# CBMINICONN.net
KiCad netlist of a schematic drawn in EAGLE
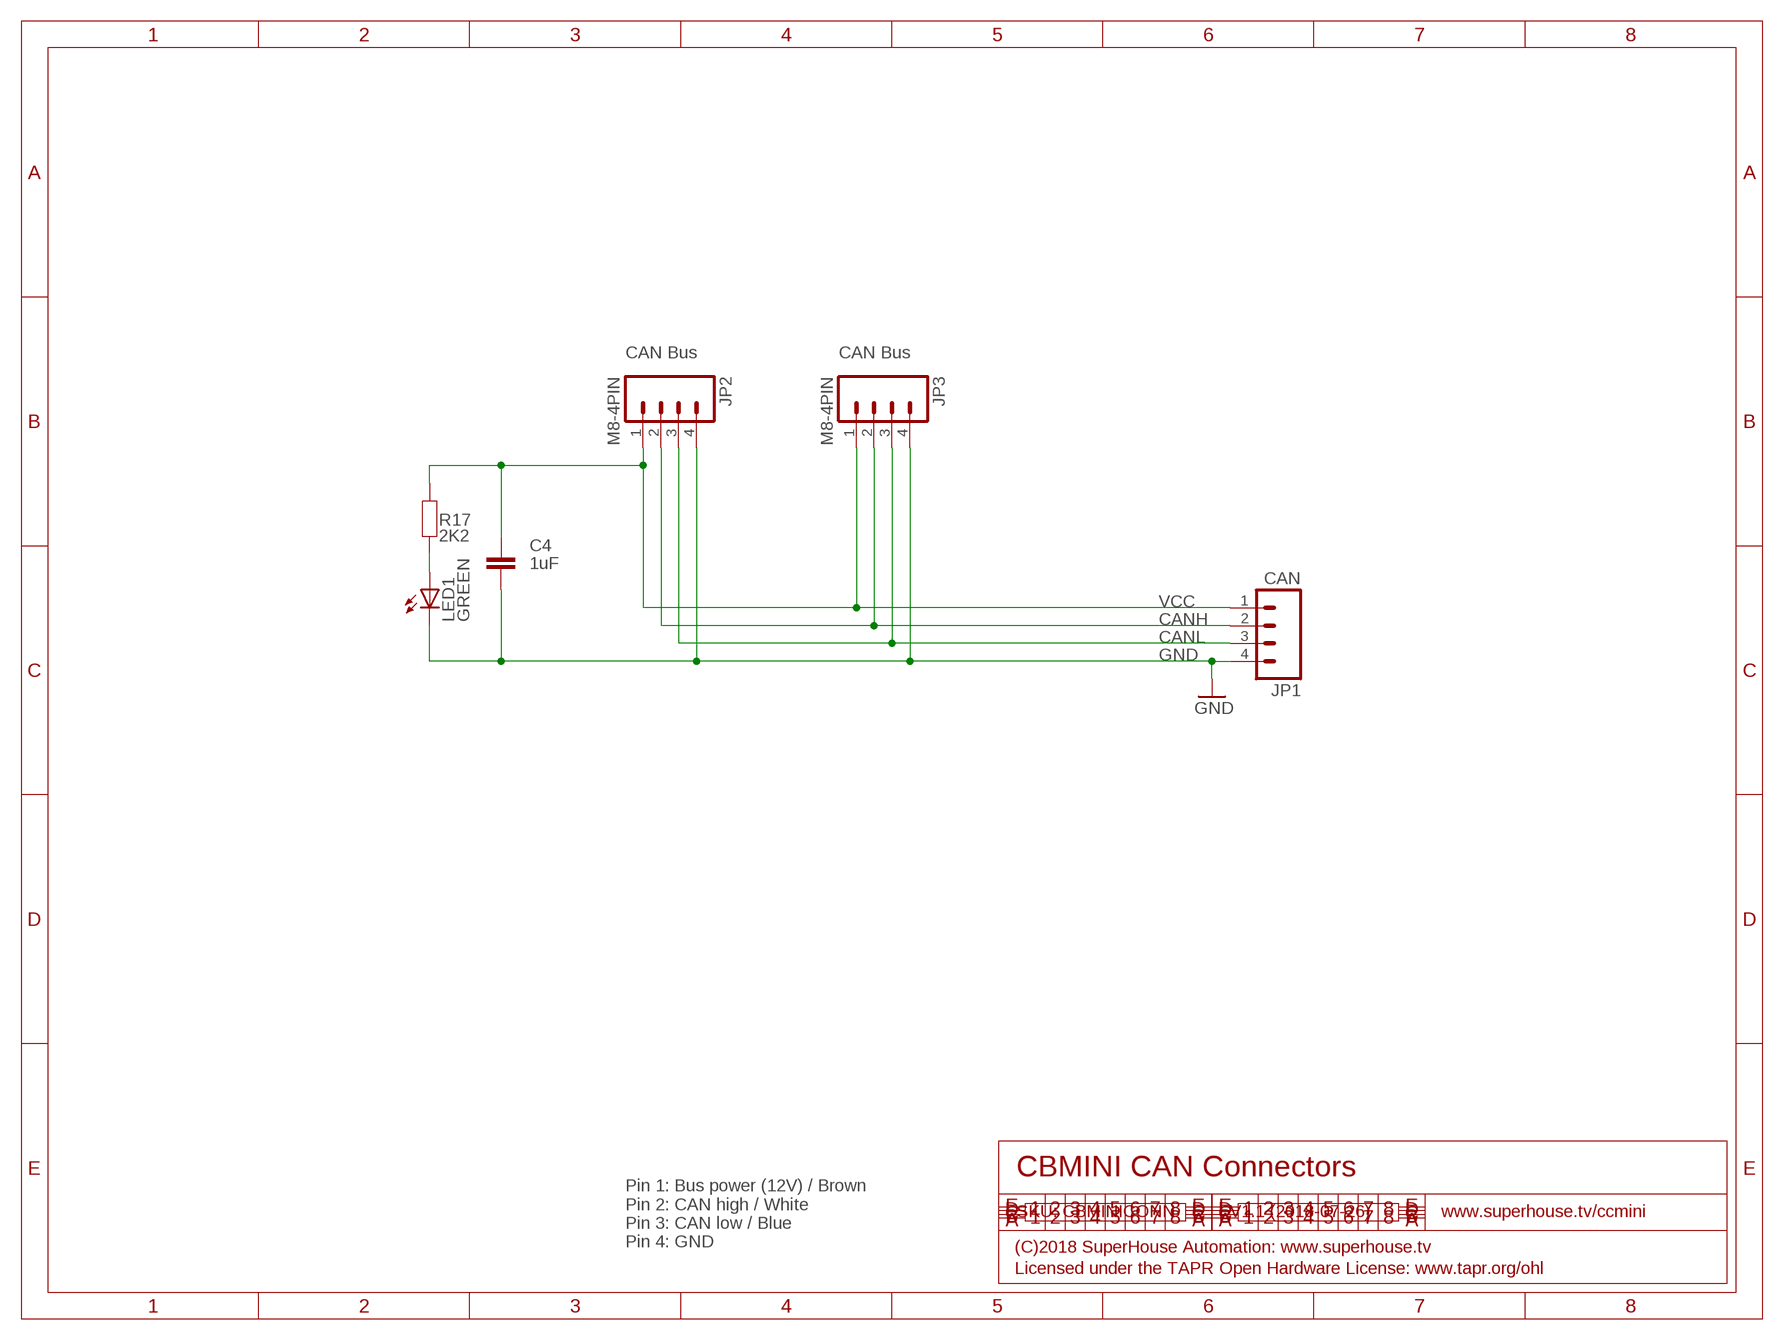
[diagram p0: schematic, sheet 1]

(export (version "E")
  (design (tool "Eeschema 10.0.6"))
  (components
    (comp (ref "C4")
      (value "1uF")
      (footprint "eagle-import:0603")
      (libsource (lib "eagle-import") (part "CAP0603"))
    )
    (comp (ref "JP1")
      (value "CAN")
      (footprint "eagle-import:1X04")
      (libsource (lib "eagle-import") (part "M04PTH"))
    )
    (comp (ref "JP2")
      (value "M8-4PIN")
      (footprint "eagle-import:M8-4PIN")
      (libsource (lib "eagle-import") (part "M8-4PIN"))
    )
    (comp (ref "JP3")
      (value "M8-4PIN")
      (footprint "eagle-import:M8-4PIN")
      (libsource (lib "eagle-import") (part "M8-4PIN"))
    )
    (comp (ref "LED1")
      (value "GREEN")
      (footprint "eagle-import:LED3MM")
      (libsource (lib "eagle-import") (part "LED3MM"))
    )
    (comp (ref "R17")
      (value "2K2")
      (footprint "eagle-import:0603")
      (libsource (lib "eagle-import") (part "RESISTOR0603"))
    )
  )
  (nets
    (net (code "1") (name "/CANH") (class "Default")
      (node (ref "JP1") (pin "2") (pinfunction "2_2") (pintype "passive"))
      (node (ref "JP2") (pin "2") (pinfunction "2_2") (pintype "passive"))
      (node (ref "JP3") (pin "2") (pinfunction "2_2") (pintype "passive"))
    )
    (net (code "2") (name "/CANL") (class "Default")
      (node (ref "JP1") (pin "3") (pinfunction "3_3") (pintype "passive"))
      (node (ref "JP2") (pin "3") (pinfunction "3_3") (pintype "passive"))
      (node (ref "JP3") (pin "3") (pinfunction "3_3") (pintype "passive"))
    )
    (net (code "3") (name "/VCC") (class "Default")
      (node (ref "C4") (pin "2") (pinfunction "2_2") (pintype "passive"))
      (node (ref "JP1") (pin "1") (pinfunction "1_1") (pintype "passive"))
      (node (ref "JP2") (pin "1") (pinfunction "1_1") (pintype "passive"))
      (node (ref "JP3") (pin "1") (pinfunction "1_1") (pintype "passive"))
      (node (ref "R17") (pin "2") (pinfunction "2_2") (pintype "passive"))
    )
    (net (code "4") (name "GND") (class "Default")
      (node (ref "C4") (pin "1") (pinfunction "1_1") (pintype "passive"))
      (node (ref "JP1") (pin "4") (pinfunction "4_4") (pintype "passive"))
      (node (ref "JP2") (pin "4") (pinfunction "4_4") (pintype "passive"))
      (node (ref "JP3") (pin "4") (pinfunction "4_4") (pintype "passive"))
      (node (ref "LED1") (pin "K") (pinfunction "C_K") (pintype "passive"))
    )
    (net (code "5") (name "Net-(LED1-PadA)") (class "Default")
      (node (ref "LED1") (pin "A") (pinfunction "A_A") (pintype "passive"))
      (node (ref "R17") (pin "1") (pinfunction "1_1") (pintype "passive"))
    )
  )
)
